# MaxModule.net
KiCad netlist of a schematic drawn in Altium Designer
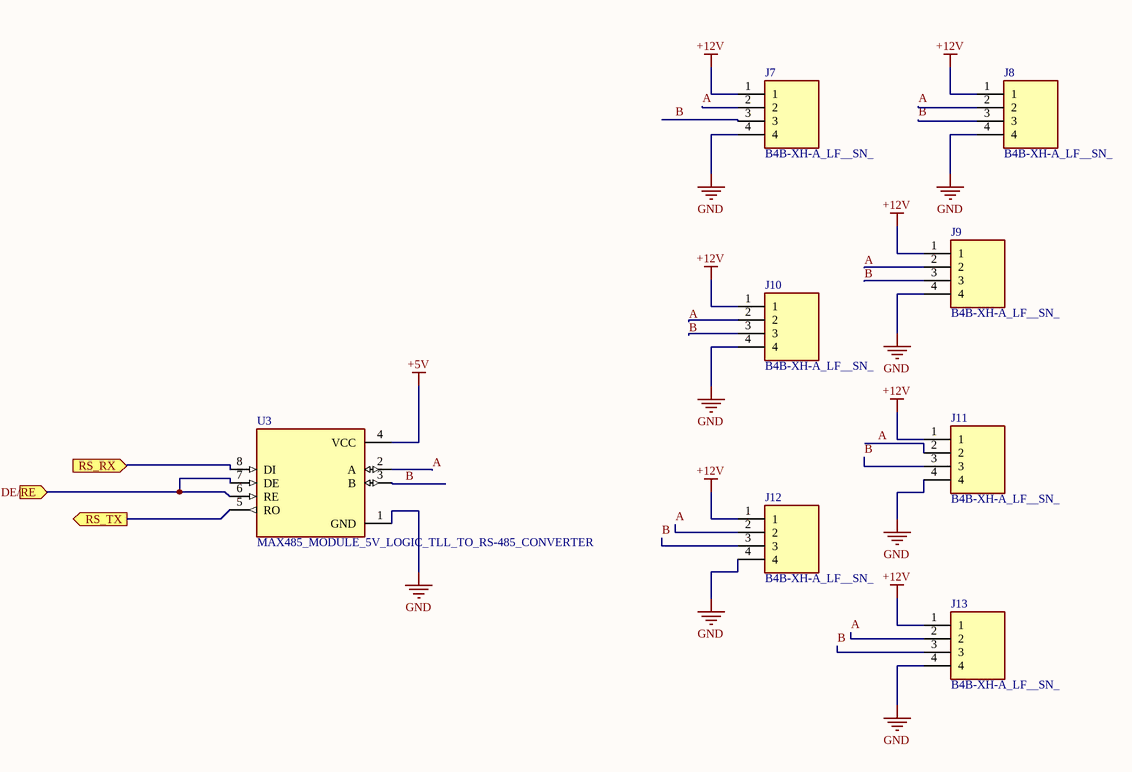
[diagram p0: MaxModule.SchDoc]

(export (version "E")
  (design (tool "Eeschema 10.0.6"))
  (components
    (comp (ref "J7")
      (value "B4B-XH-A_LF__SN_")
      (footprint "SamacSys:B4BXHALFSN")
      (description "Connector")
      (fields
        (field (name "MANUFACTURER_PART_NUMBER") "B4B-XH-A(LF)(SN)")
        (field (name "MOUSER PART NUMBER") "306-B4BXHALFSN")
      )
      (libsource (lib "SchlibpolyESP") (part "B4B-XH-A_LF__SN_"))
    )
    (comp (ref "J8")
      (value "B4B-XH-A_LF__SN_")
      (footprint "SamacSys:B4BXHALFSN")
      (description "Connector")
      (fields
        (field (name "MANUFACTURER_PART_NUMBER") "B4B-XH-A(LF)(SN)")
        (field (name "MOUSER PART NUMBER") "306-B4BXHALFSN")
      )
      (libsource (lib "SchlibpolyESP") (part "B4B-XH-A_LF__SN_"))
    )
    (comp (ref "J9")
      (value "B4B-XH-A_LF__SN_")
      (footprint "SamacSys:B4BXHALFSN")
      (description "Connector")
      (fields
        (field (name "MANUFACTURER_PART_NUMBER") "B4B-XH-A(LF)(SN)")
        (field (name "MOUSER PART NUMBER") "306-B4BXHALFSN")
      )
      (libsource (lib "SchlibpolyESP") (part "B4B-XH-A_LF__SN_"))
    )
    (comp (ref "J10")
      (value "B4B-XH-A_LF__SN_")
      (footprint "SamacSys:B4BXHALFSN")
      (description "Connector")
      (fields
        (field (name "MANUFACTURER_PART_NUMBER") "B4B-XH-A(LF)(SN)")
        (field (name "MOUSER PART NUMBER") "306-B4BXHALFSN")
      )
      (libsource (lib "SchlibpolyESP") (part "B4B-XH-A_LF__SN_"))
    )
    (comp (ref "J11")
      (value "B4B-XH-A_LF__SN_")
      (footprint "SamacSys:B4BXHALFSN")
      (description "Connector")
      (fields
        (field (name "MANUFACTURER_PART_NUMBER") "B4B-XH-A(LF)(SN)")
        (field (name "MOUSER PART NUMBER") "306-B4BXHALFSN")
      )
      (libsource (lib "SchlibpolyESP") (part "B4B-XH-A_LF__SN_"))
    )
    (comp (ref "J12")
      (value "B4B-XH-A_LF__SN_")
      (footprint "SamacSys:B4BXHALFSN")
      (description "Connector")
      (fields
        (field (name "MANUFACTURER_PART_NUMBER") "B4B-XH-A(LF)(SN)")
        (field (name "MOUSER PART NUMBER") "306-B4BXHALFSN")
      )
      (libsource (lib "SchlibpolyESP") (part "B4B-XH-A_LF__SN_"))
    )
    (comp (ref "J13")
      (value "B4B-XH-A_LF__SN_")
      (footprint "SamacSys:B4BXHALFSN")
      (description "Connector")
      (fields
        (field (name "MANUFACTURER_PART_NUMBER") "B4B-XH-A(LF)(SN)")
        (field (name "MOUSER PART NUMBER") "306-B4BXHALFSN")
      )
      (libsource (lib "SchlibpolyESP") (part "B4B-XH-A_LF__SN_"))
    )
    (comp (ref "U3")
      (value "MAX485_MODULE_5V_LOGIC_TLL_TO_RS-485_CONVERTER")
      (footprint "MODULE_MAX485_MODULE_5V_LOGIC_TLL_TO_RS-485_CONVERTER")
      (description "5V MAX485 TTL To RS485 Converter Module Board for Arduino")
      (fields
        (field (name "MP") "MAX485 Module 5V logic TLL to RS-485 converter")
        (field (name "MF") "e-Gizmo Mechatronix Central")
      )
      (libsource (lib "SchlibpolyESP") (part "MAX485_MODULE_5V_LOGIC_TLL_TO_RS-485_CONVERTER"))
    )
  )
  (nets
    (net (code "1") (name "+5V") (class "Default")
      (node (ref "U3") (pin "4") (pinfunction "VCC_4") (pintype "power_in"))
    )
    (net (code "2") (name "+12V") (class "Default")
      (node (ref "J10") (pin "1") (pinfunction "1_1") (pintype "passive"))
      (node (ref "J11") (pin "1") (pinfunction "1_1") (pintype "passive"))
      (node (ref "J12") (pin "1") (pinfunction "1_1") (pintype "passive"))
      (node (ref "J13") (pin "1") (pinfunction "1_1") (pintype "passive"))
      (node (ref "J7") (pin "1") (pinfunction "1_1") (pintype "passive"))
      (node (ref "J8") (pin "1") (pinfunction "1_1") (pintype "passive"))
      (node (ref "J9") (pin "1") (pinfunction "1_1") (pintype "passive"))
    )
    (net (code "3") (name "/A") (class "Default")
      (node (ref "J10") (pin "2") (pinfunction "2_2") (pintype "passive"))
      (node (ref "J11") (pin "2") (pinfunction "2_2") (pintype "passive"))
      (node (ref "J12") (pin "2") (pinfunction "2_2") (pintype "passive"))
      (node (ref "J13") (pin "2") (pinfunction "2_2") (pintype "passive"))
      (node (ref "J7") (pin "2") (pinfunction "2_2") (pintype "passive"))
      (node (ref "J8") (pin "2") (pinfunction "2_2") (pintype "passive"))
      (node (ref "J9") (pin "2") (pinfunction "2_2") (pintype "passive"))
      (node (ref "U3") (pin "2") (pinfunction "A_2") (pintype "bidirectional"))
    )
    (net (code "4") (name "/B") (class "Default")
      (node (ref "J10") (pin "3") (pinfunction "3_3") (pintype "passive"))
      (node (ref "J11") (pin "3") (pinfunction "3_3") (pintype "passive"))
      (node (ref "J12") (pin "3") (pinfunction "3_3") (pintype "passive"))
      (node (ref "J13") (pin "3") (pinfunction "3_3") (pintype "passive"))
      (node (ref "J7") (pin "3") (pinfunction "3_3") (pintype "passive"))
      (node (ref "J8") (pin "3") (pinfunction "3_3") (pintype "passive"))
      (node (ref "J9") (pin "3") (pinfunction "3_3") (pintype "passive"))
      (node (ref "U3") (pin "3") (pinfunction "B_3") (pintype "bidirectional"))
    )
    (net (code "5") (name "/DE{slash}RE") (class "Default")
      (node (ref "U3") (pin "6") (pinfunction "RE_6") (pintype "input"))
      (node (ref "U3") (pin "7") (pinfunction "DE_7") (pintype "input"))
    )
    (net (code "6") (name "/RS_RX") (class "Default")
      (node (ref "U3") (pin "8") (pinfunction "DI_8") (pintype "input"))
    )
    (net (code "7") (name "/RS_TX") (class "Default")
      (node (ref "U3") (pin "5") (pinfunction "RO_5") (pintype "output"))
    )
    (net (code "8") (name "GND") (class "Default")
      (node (ref "J10") (pin "4") (pinfunction "4_4") (pintype "passive"))
      (node (ref "J11") (pin "4") (pinfunction "4_4") (pintype "passive"))
      (node (ref "J12") (pin "4") (pinfunction "4_4") (pintype "passive"))
      (node (ref "J13") (pin "4") (pinfunction "4_4") (pintype "passive"))
      (node (ref "J7") (pin "4") (pinfunction "4_4") (pintype "passive"))
      (node (ref "J8") (pin "4") (pinfunction "4_4") (pintype "passive"))
      (node (ref "J9") (pin "4") (pinfunction "4_4") (pintype "passive"))
      (node (ref "U3") (pin "1") (pinfunction "GND_1") (pintype "power_in"))
    )
  )
)
